# Sch.net
KiCad netlist of a schematic drawn in EAGLE
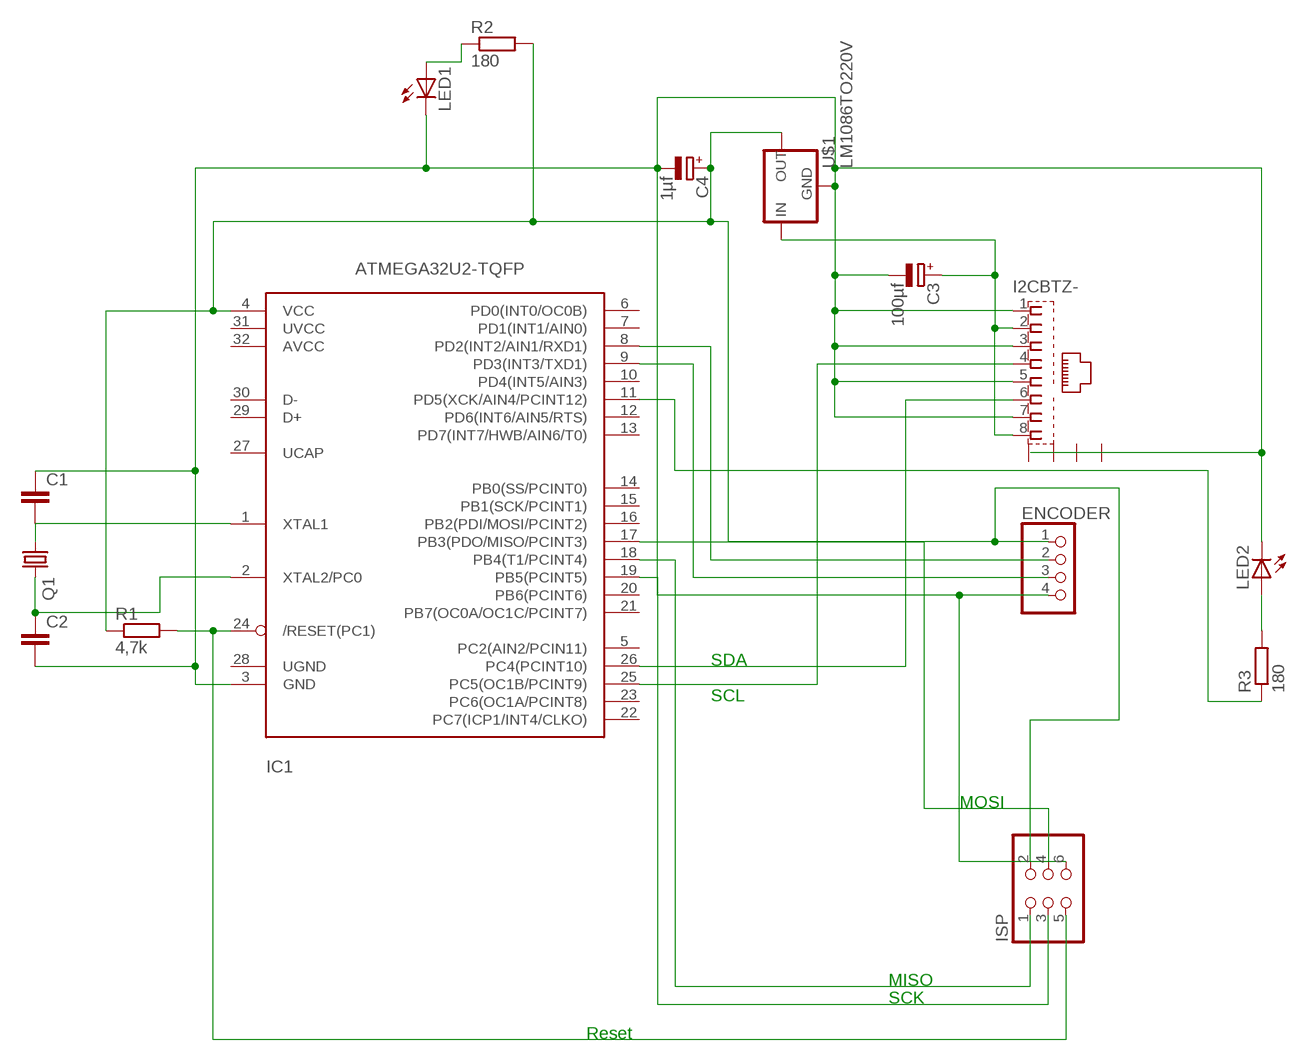
[diagram p0: schematic, sheet 1]

(export (version "E")
  (design (tool "Eeschema 10.0.6"))
  (components
    (comp (ref "C1")
      (value "C-EU025-025X050")
      (footprint "eagle-import:C025-025X050")
      (libsource (lib "eagle-import") (part "C-EU025-025X050"))
    )
    (comp (ref "C2")
      (value "C-EU025-025X050")
      (footprint "eagle-import:C025-025X050")
      (libsource (lib "eagle-import") (part "C-EU025-025X050"))
    )
    (comp (ref "C3")
      (value "100µf")
      (footprint "eagle-import:E2,5-6")
      (libsource (lib "eagle-import") (part "CPOL-EUE2.5-6"))
    )
    (comp (ref "C4")
      (value "1µf")
      (footprint "eagle-import:E2,5-6")
      (libsource (lib "eagle-import") (part "CPOL-EUE2.5-6"))
    )
    (comp (ref "ENCODER")
      (value "PINHD-1X4")
      (footprint "eagle-import:1X04")
      (libsource (lib "eagle-import") (part "PINHD-1X4"))
    )
    (comp (ref "I2CBTZ")
      (value "RJ45")
      (footprint "eagle-import:RJ45")
      (libsource (lib "eagle-import") (part "RJ45"))
    )
    (comp (ref "IC1")
      (value "ATMEGA32U2-TQFP")
      (footprint "eagle-import:TQFP32-08")
      (libsource (lib "eagle-import") (part "ATMEGA32U2-TQFP"))
    )
    (comp (ref "ISP")
      (value "PINHD-2X3")
      (footprint "eagle-import:2X03")
      (libsource (lib "eagle-import") (part "PINHD-2X3"))
    )
    (comp (ref "LED1")
      (value "LED5MM")
      (footprint "eagle-import:LED5MM")
      (libsource (lib "eagle-import") (part "LED5MM"))
    )
    (comp (ref "LED2")
      (value "LED5MM")
      (footprint "eagle-import:LED5MM")
      (libsource (lib "eagle-import") (part "LED5MM"))
    )
    (comp (ref "Q1")
      (value "CRYSTALHC49S")
      (footprint "eagle-import:HC49_S")
      (libsource (lib "eagle-import") (part "CRYSTALHC49S"))
    )
    (comp (ref "R1")
      (value "4,7k")
      (footprint "eagle-import:0204_7")
      (libsource (lib "eagle-import") (part "R-EU_0204/7"))
    )
    (comp (ref "R2")
      (value "180")
      (footprint "eagle-import:0204_7")
      (libsource (lib "eagle-import") (part "R-EU_0204/7"))
    )
    (comp (ref "R3")
      (value "180")
      (footprint "eagle-import:0204_7")
      (libsource (lib "eagle-import") (part "R-EU_0204/7"))
    )
    (comp (ref "U$1")
      (value "LM1086TO220V")
      (footprint "eagle-import:TO220S")
      (libsource (lib "eagle-import") (part "LM1086TO220V"))
    )
  )
  (nets
    (net (code "1") (name "Net-(IC1-GND)") (class "Default")
      (node (ref "C1") (pin "1") (pinfunction "1_1") (pintype "passive"))
      (node (ref "C2") (pin "2") (pinfunction "2_2") (pintype "passive"))
      (node (ref "C3") (pin "-") (pinfunction "-_-") (pintype "passive"))
      (node (ref "C4") (pin "-") (pinfunction "-_-") (pintype "passive"))
      (node (ref "ENCODER") (pin "4") (pinfunction "4_4") (pintype "passive"))
      (node (ref "I2CBTZ") (pin "1") (pinfunction "1_1") (pintype "passive"))
      (node (ref "I2CBTZ") (pin "3") (pinfunction "3_3") (pintype "passive"))
      (node (ref "I2CBTZ") (pin "5") (pinfunction "5_5") (pintype "passive"))
      (node (ref "I2CBTZ") (pin "7") (pinfunction "7_7") (pintype "passive"))
      (node (ref "IC1") (pin "3") (pinfunction "GND_3") (pintype "bidirectional"))
      (node (ref "ISP") (pin "6") (pinfunction "6_6") (pintype "passive"))
      (node (ref "LED1") (pin "K") (pinfunction "C_K") (pintype "passive"))
      (node (ref "LED2") (pin "K") (pinfunction "C_K") (pintype "passive"))
      (node (ref "U$1") (pin "1") (pinfunction "GND_1") (pintype "input"))
    )
    (net (code "2") (name "Net-(IC1-PB3(PDO{slash}MISO{slash}PCINT3))") (class "Default")
      (node (ref "IC1") (pin "17") (pinfunction "PB3(PDO/MISO/PCINT3)_17") (pintype "bidirectional"))
      (node (ref "ISP") (pin "4") (pinfunction "4_4") (pintype "passive"))
    )
    (net (code "3") (name "Net-(IC1-PB4(T1{slash}PCINT4))") (class "Default")
      (node (ref "IC1") (pin "18") (pinfunction "PB4(T1/PCINT4)_18") (pintype "bidirectional"))
      (node (ref "ISP") (pin "1") (pinfunction "1_1") (pintype "passive"))
    )
    (net (code "4") (name "Net-(IC1-PB5(PCINT5))") (class "Default")
      (node (ref "IC1") (pin "19") (pinfunction "PB5(PCINT5)_19") (pintype "bidirectional"))
      (node (ref "ISP") (pin "3") (pinfunction "3_3") (pintype "passive"))
    )
    (net (code "5") (name "Net-(IC1-PC4(PCINT10))") (class "Default")
      (node (ref "I2CBTZ") (pin "6") (pinfunction "6_6") (pintype "passive"))
      (node (ref "IC1") (pin "26") (pinfunction "PC4(PCINT10)_26") (pintype "bidirectional"))
    )
    (net (code "6") (name "Net-(IC1-PC5(OC1B{slash}PCINT9))") (class "Default")
      (node (ref "I2CBTZ") (pin "4") (pinfunction "4_4") (pintype "passive"))
      (node (ref "IC1") (pin "25") (pinfunction "PC5(OC1B/PCINT9)_25") (pintype "bidirectional"))
    )
    (net (code "7") (name "Net-(IC1-PD2(INT2{slash}AIN1{slash}RXD1))") (class "Default")
      (node (ref "ENCODER") (pin "2") (pinfunction "2_2") (pintype "passive"))
      (node (ref "IC1") (pin "8") (pinfunction "PD2(INT2/AIN1/RXD1)_8") (pintype "bidirectional"))
    )
    (net (code "8") (name "Net-(IC1-PD3(INT3{slash}TXD1))") (class "Default")
      (node (ref "ENCODER") (pin "3") (pinfunction "3_3") (pintype "passive"))
      (node (ref "IC1") (pin "9") (pinfunction "PD3(INT3/TXD1)_9") (pintype "bidirectional"))
    )
    (net (code "9") (name "Net-(IC1-PD5(XCK{slash}AIN4{slash}PCINT12))") (class "Default")
      (node (ref "IC1") (pin "11") (pinfunction "PD5(XCK/AIN4/PCINT12)_11") (pintype "bidirectional"))
      (node (ref "R3") (pin "1") (pinfunction "1_1") (pintype "passive"))
    )
    (net (code "10") (name "Net-(IC1-VCC)") (class "Default")
      (node (ref "C4") (pin "+") (pinfunction "+_+") (pintype "passive"))
      (node (ref "ENCODER") (pin "1") (pinfunction "1_1") (pintype "passive"))
      (node (ref "IC1") (pin "4") (pinfunction "VCC_4") (pintype "bidirectional"))
      (node (ref "ISP") (pin "2") (pinfunction "2_2") (pintype "passive"))
      (node (ref "R1") (pin "1") (pinfunction "1_1") (pintype "passive"))
      (node (ref "R2") (pin "2") (pinfunction "2_2") (pintype "passive"))
      (node (ref "U$1") (pin "2") (pinfunction "OUT_2") (pintype "passive"))
    )
    (net (code "11") (name "Net-(IC1-XTAL1)") (class "Default")
      (node (ref "C1") (pin "2") (pinfunction "2_2") (pintype "passive"))
      (node (ref "IC1") (pin "1") (pinfunction "XTAL1_1") (pintype "bidirectional"))
      (node (ref "Q1") (pin "1") (pinfunction "1_1") (pintype "passive"))
    )
    (net (code "12") (name "Net-(IC1-XTAL2{slash}PC0)") (class "Default")
      (node (ref "C2") (pin "1") (pinfunction "1_1") (pintype "passive"))
      (node (ref "IC1") (pin "2") (pinfunction "XTAL2/PC0_2") (pintype "bidirectional"))
      (node (ref "Q1") (pin "2") (pinfunction "2_2") (pintype "passive"))
    )
    (net (code "13") (name "Net-(IC1-{slash}RESET(PC1))") (class "Default")
      (node (ref "IC1") (pin "24") (pinfunction "/RESET(PC1)_24") (pintype "bidirectional"))
      (node (ref "ISP") (pin "5") (pinfunction "5_5") (pintype "passive"))
      (node (ref "R1") (pin "2") (pinfunction "2_2") (pintype "passive"))
    )
    (net (code "14") (name "Net-(LED1-PadA)") (class "Default")
      (node (ref "LED1") (pin "A") (pinfunction "A_A") (pintype "passive"))
      (node (ref "R2") (pin "1") (pinfunction "1_1") (pintype "passive"))
    )
    (net (code "15") (name "Net-(LED2-PadA)") (class "Default")
      (node (ref "LED2") (pin "A") (pinfunction "A_A") (pintype "passive"))
      (node (ref "R3") (pin "2") (pinfunction "2_2") (pintype "passive"))
    )
    (net (code "16") (name "Net-(U$1-IN)") (class "Default")
      (node (ref "C3") (pin "+") (pinfunction "+_+") (pintype "passive"))
      (node (ref "I2CBTZ") (pin "2") (pinfunction "2_2") (pintype "passive"))
      (node (ref "I2CBTZ") (pin "8") (pinfunction "8_8") (pintype "passive"))
      (node (ref "U$1") (pin "3") (pinfunction "IN_3") (pintype "input"))
    )
    (net (code "17") (name "unconnected-(I2CBTZB-1-PadG1)") (class "Default")
      (node (ref "I2CBTZ") (pin "G1") (pinfunction "1_G1") (pintype "passive"))
    )
    (net (code "18") (name "unconnected-(I2CBTZC-1-PadG2)") (class "Default")
      (node (ref "I2CBTZ") (pin "G2") (pinfunction "1_G2") (pintype "passive"))
    )
    (net (code "19") (name "unconnected-(I2CBTZD-1-PadG3)") (class "Default")
      (node (ref "I2CBTZ") (pin "G3") (pinfunction "1_G3") (pintype "passive"))
    )
    (net (code "20") (name "unconnected-(I2CBTZE-1-PadG4)") (class "Default")
      (node (ref "I2CBTZ") (pin "G4") (pinfunction "1_G4") (pintype "passive"))
    )
    (net (code "21") (name "unconnected-(IC1-AVCC-Pad32)") (class "Default")
      (node (ref "IC1") (pin "32") (pinfunction "AVCC_32") (pintype "bidirectional"))
    )
    (net (code "22") (name "unconnected-(IC1-D+-Pad29)") (class "Default")
      (node (ref "IC1") (pin "29") (pinfunction "D+_29") (pintype "bidirectional"))
    )
    (net (code "23") (name "unconnected-(IC1-D--Pad30)") (class "Default")
      (node (ref "IC1") (pin "30") (pinfunction "D-_30") (pintype "bidirectional"))
    )
    (net (code "24") (name "unconnected-(IC1-PB0(SS{slash}PCINT0)-Pad14)") (class "Default")
      (node (ref "IC1") (pin "14") (pinfunction "PB0(SS/PCINT0)_14") (pintype "bidirectional"))
    )
    (net (code "25") (name "unconnected-(IC1-PB1(SCK{slash}PCINT1)-Pad15)") (class "Default")
      (node (ref "IC1") (pin "15") (pinfunction "PB1(SCK/PCINT1)_15") (pintype "bidirectional"))
    )
    (net (code "26") (name "unconnected-(IC1-PB2(PDI{slash}MOSI{slash}PCINT2)-Pad16)") (class "Default")
      (node (ref "IC1") (pin "16") (pinfunction "PB2(PDI/MOSI/PCINT2)_16") (pintype "bidirectional"))
    )
    (net (code "27") (name "unconnected-(IC1-PB6(PCINT6)-Pad20)") (class "Default")
      (node (ref "IC1") (pin "20") (pinfunction "PB6(PCINT6)_20") (pintype "bidirectional"))
    )
    (net (code "28") (name "unconnected-(IC1-PB7(OC0A{slash}OC1C{slash}PCINT7)-Pad21)") (class "Default")
      (node (ref "IC1") (pin "21") (pinfunction "PB7(OC0A/OC1C/PCINT7)_21") (pintype "bidirectional"))
    )
    (net (code "29") (name "unconnected-(IC1-PC2(AIN2{slash}PCIN11)-Pad5)") (class "Default")
      (node (ref "IC1") (pin "5") (pinfunction "PC2(AIN2/PCIN11)_5") (pintype "bidirectional"))
    )
    (net (code "30") (name "unconnected-(IC1-PC6(OC1A{slash}PCINT8)-Pad23)") (class "Default")
      (node (ref "IC1") (pin "23") (pinfunction "PC6(OC1A/PCINT8)_23") (pintype "bidirectional"))
    )
    (net (code "31") (name "unconnected-(IC1-PC7(ICP1{slash}INT4{slash}CLKO)-Pad22)") (class "Default")
      (node (ref "IC1") (pin "22") (pinfunction "PC7(ICP1/INT4/CLKO)_22") (pintype "bidirectional"))
    )
    (net (code "32") (name "unconnected-(IC1-PD0(INT0{slash}OC0B)-Pad6)") (class "Default")
      (node (ref "IC1") (pin "6") (pinfunction "PD0(INT0/OC0B)_6") (pintype "bidirectional"))
    )
    (net (code "33") (name "unconnected-(IC1-PD1(INT1{slash}AIN0)-Pad7)") (class "Default")
      (node (ref "IC1") (pin "7") (pinfunction "PD1(INT1/AIN0)_7") (pintype "bidirectional"))
    )
    (net (code "34") (name "unconnected-(IC1-PD4(INT5{slash}AIN3)-Pad10)") (class "Default")
      (node (ref "IC1") (pin "10") (pinfunction "PD4(INT5/AIN3)_10") (pintype "bidirectional"))
    )
    (net (code "35") (name "unconnected-(IC1-PD6(INT6{slash}AIN5{slash}RTS)-Pad12)") (class "Default")
      (node (ref "IC1") (pin "12") (pinfunction "PD6(INT6/AIN5/RTS)_12") (pintype "bidirectional"))
    )
    (net (code "36") (name "unconnected-(IC1-PD7(INT7{slash}HWB{slash}AIN6{slash}T0)-Pad13)") (class "Default")
      (node (ref "IC1") (pin "13") (pinfunction "PD7(INT7/HWB/AIN6/T0)_13") (pintype "bidirectional"))
    )
    (net (code "37") (name "unconnected-(IC1-UCAP-Pad27)") (class "Default")
      (node (ref "IC1") (pin "27") (pinfunction "UCAP_27") (pintype "bidirectional"))
    )
    (net (code "38") (name "unconnected-(IC1-UGND-Pad28)") (class "Default")
      (node (ref "IC1") (pin "28") (pinfunction "UGND_28") (pintype "bidirectional"))
    )
    (net (code "39") (name "unconnected-(IC1-UVCC-Pad31)") (class "Default")
      (node (ref "IC1") (pin "31") (pinfunction "UVCC_31") (pintype "bidirectional"))
    )
  )
)
